# Sunfish_ECU_BulkCaps_RevA.net
KiCad netlist of a schematic drawn in Altium Designer
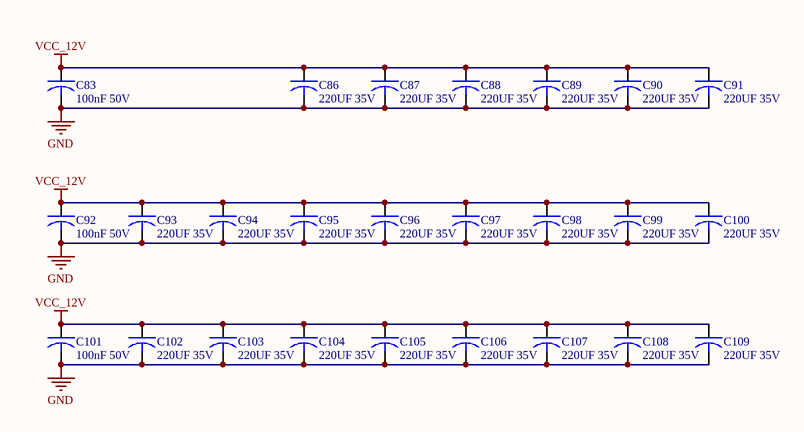
[diagram p0: Sunfish_ECU_BulkCaps_RevA.SchDoc]

(export (version "E")
  (design (tool "Eeschema 10.0.6"))
  (components
    (comp (ref "C83")
      (value "100nF 50V")
      (footprint "0603")
      (description "CAP CER 100nF 50V 10% X7R 0603")
      (fields (field (name "MANUFACTURER") "Murata"))
      (libsource (lib "Caps") (part "CAP_100NF_50V_10%_0603"))
    )
    (comp (ref "C86")
      (value "220UF 35V")
      (footprint "RB.15/.32")
      (description "CAP CER 220UF 35V 20%")
      (fields (field (name "MANUFACTURER") "Kemet"))
      (libsource (lib "Caps") (part "CAP_220UF_35V_20%"))
    )
    (comp (ref "C87")
      (value "220UF 35V")
      (footprint "RB.15/.32")
      (description "CAP CER 220UF 35V 20%")
      (fields (field (name "MANUFACTURER") "Kemet"))
      (libsource (lib "Caps") (part "CAP_220UF_35V_20%"))
    )
    (comp (ref "C88")
      (value "220UF 35V")
      (footprint "RB.15/.32")
      (description "CAP CER 220UF 35V 20%")
      (fields (field (name "MANUFACTURER") "Kemet"))
      (libsource (lib "Caps") (part "CAP_220UF_35V_20%"))
    )
    (comp (ref "C89")
      (value "220UF 35V")
      (footprint "RB.15/.32")
      (description "CAP CER 220UF 35V 20%")
      (fields (field (name "MANUFACTURER") "Kemet"))
      (libsource (lib "Caps") (part "CAP_220UF_35V_20%"))
    )
    (comp (ref "C90")
      (value "220UF 35V")
      (footprint "RB.15/.32")
      (description "CAP CER 220UF 35V 20%")
      (fields (field (name "MANUFACTURER") "Kemet"))
      (libsource (lib "Caps") (part "CAP_220UF_35V_20%"))
    )
    (comp (ref "C91")
      (value "220UF 35V")
      (footprint "RB.15/.32")
      (description "CAP CER 220UF 35V 20%")
      (fields (field (name "MANUFACTURER") "Kemet"))
      (libsource (lib "Caps") (part "CAP_220UF_35V_20%"))
    )
    (comp (ref "C92")
      (value "100nF 50V")
      (footprint "0603")
      (description "CAP CER 100nF 50V 10% X7R 0603")
      (fields (field (name "MANUFACTURER") "Murata"))
      (libsource (lib "Caps") (part "CAP_100NF_50V_10%_0603"))
    )
    (comp (ref "C93")
      (value "220UF 35V")
      (footprint "RB.15/.32")
      (description "CAP CER 220UF 35V 20%")
      (fields (field (name "MANUFACTURER") "Kemet"))
      (libsource (lib "Caps") (part "CAP_220UF_35V_20%"))
    )
    (comp (ref "C94")
      (value "220UF 35V")
      (footprint "RB.15/.32")
      (description "CAP CER 220UF 35V 20%")
      (fields (field (name "MANUFACTURER") "Kemet"))
      (libsource (lib "Caps") (part "CAP_220UF_35V_20%"))
    )
    (comp (ref "C95")
      (value "220UF 35V")
      (footprint "RB.15/.32")
      (description "CAP CER 220UF 35V 20%")
      (fields (field (name "MANUFACTURER") "Kemet"))
      (libsource (lib "Caps") (part "CAP_220UF_35V_20%"))
    )
    (comp (ref "C96")
      (value "220UF 35V")
      (footprint "RB.15/.32")
      (description "CAP CER 220UF 35V 20%")
      (fields (field (name "MANUFACTURER") "Kemet"))
      (libsource (lib "Caps") (part "CAP_220UF_35V_20%"))
    )
    (comp (ref "C97")
      (value "220UF 35V")
      (footprint "RB.15/.32")
      (description "CAP CER 220UF 35V 20%")
      (fields (field (name "MANUFACTURER") "Kemet"))
      (libsource (lib "Caps") (part "CAP_220UF_35V_20%"))
    )
    (comp (ref "C98")
      (value "220UF 35V")
      (footprint "RB.15/.32")
      (description "CAP CER 220UF 35V 20%")
      (fields (field (name "MANUFACTURER") "Kemet"))
      (libsource (lib "Caps") (part "CAP_220UF_35V_20%"))
    )
    (comp (ref "C99")
      (value "220UF 35V")
      (footprint "RB.15/.32")
      (description "CAP CER 220UF 35V 20%")
      (fields (field (name "MANUFACTURER") "Kemet"))
      (libsource (lib "Caps") (part "CAP_220UF_35V_20%"))
    )
    (comp (ref "C100")
      (value "220UF 35V")
      (footprint "RB.15/.32")
      (description "CAP CER 220UF 35V 20%")
      (fields (field (name "MANUFACTURER") "Kemet"))
      (libsource (lib "Caps") (part "CAP_220UF_35V_20%"))
    )
    (comp (ref "C101")
      (value "100nF 50V")
      (footprint "0603")
      (description "CAP CER 100nF 50V 10% X7R 0603")
      (fields (field (name "MANUFACTURER") "Murata"))
      (libsource (lib "Caps") (part "CAP_100NF_50V_10%_0603"))
    )
    (comp (ref "C102")
      (value "220UF 35V")
      (footprint "RB.15/.32")
      (description "CAP CER 220UF 35V 20%")
      (fields (field (name "MANUFACTURER") "Kemet"))
      (libsource (lib "Caps") (part "CAP_220UF_35V_20%"))
    )
    (comp (ref "C103")
      (value "220UF 35V")
      (footprint "RB.15/.32")
      (description "CAP CER 220UF 35V 20%")
      (fields (field (name "MANUFACTURER") "Kemet"))
      (libsource (lib "Caps") (part "CAP_220UF_35V_20%"))
    )
    (comp (ref "C104")
      (value "220UF 35V")
      (footprint "RB.15/.32")
      (description "CAP CER 220UF 35V 20%")
      (fields (field (name "MANUFACTURER") "Kemet"))
      (libsource (lib "Caps") (part "CAP_220UF_35V_20%"))
    )
    (comp (ref "C105")
      (value "220UF 35V")
      (footprint "RB.15/.32")
      (description "CAP CER 220UF 35V 20%")
      (fields (field (name "MANUFACTURER") "Kemet"))
      (libsource (lib "Caps") (part "CAP_220UF_35V_20%"))
    )
    (comp (ref "C106")
      (value "220UF 35V")
      (footprint "RB.15/.32")
      (description "CAP CER 220UF 35V 20%")
      (fields (field (name "MANUFACTURER") "Kemet"))
      (libsource (lib "Caps") (part "CAP_220UF_35V_20%"))
    )
    (comp (ref "C107")
      (value "220UF 35V")
      (footprint "RB.15/.32")
      (description "CAP CER 220UF 35V 20%")
      (fields (field (name "MANUFACTURER") "Kemet"))
      (libsource (lib "Caps") (part "CAP_220UF_35V_20%"))
    )
    (comp (ref "C108")
      (value "220UF 35V")
      (footprint "RB.15/.32")
      (description "CAP CER 220UF 35V 20%")
      (fields (field (name "MANUFACTURER") "Kemet"))
      (libsource (lib "Caps") (part "CAP_220UF_35V_20%"))
    )
    (comp (ref "C109")
      (value "220UF 35V")
      (footprint "RB.15/.32")
      (description "CAP CER 220UF 35V 20%")
      (fields (field (name "MANUFACTURER") "Kemet"))
      (libsource (lib "Caps") (part "CAP_220UF_35V_20%"))
    )
  )
  (nets
    (net (code "1") (name "GND") (class "Default")
      (node (ref "C100") (pin "2") (pinfunction "2_2") (pintype "passive"))
      (node (ref "C101") (pin "2") (pinfunction "2_2") (pintype "passive"))
      (node (ref "C102") (pin "2") (pinfunction "2_2") (pintype "passive"))
      (node (ref "C103") (pin "2") (pinfunction "2_2") (pintype "passive"))
      (node (ref "C104") (pin "2") (pinfunction "2_2") (pintype "passive"))
      (node (ref "C105") (pin "2") (pinfunction "2_2") (pintype "passive"))
      (node (ref "C106") (pin "2") (pinfunction "2_2") (pintype "passive"))
      (node (ref "C107") (pin "2") (pinfunction "2_2") (pintype "passive"))
      (node (ref "C108") (pin "2") (pinfunction "2_2") (pintype "passive"))
      (node (ref "C109") (pin "2") (pinfunction "2_2") (pintype "passive"))
      (node (ref "C83") (pin "2") (pinfunction "2_2") (pintype "passive"))
      (node (ref "C86") (pin "2") (pinfunction "2_2") (pintype "passive"))
      (node (ref "C87") (pin "2") (pinfunction "2_2") (pintype "passive"))
      (node (ref "C88") (pin "2") (pinfunction "2_2") (pintype "passive"))
      (node (ref "C89") (pin "2") (pinfunction "2_2") (pintype "passive"))
      (node (ref "C90") (pin "2") (pinfunction "2_2") (pintype "passive"))
      (node (ref "C91") (pin "2") (pinfunction "2_2") (pintype "passive"))
      (node (ref "C92") (pin "2") (pinfunction "2_2") (pintype "passive"))
      (node (ref "C93") (pin "2") (pinfunction "2_2") (pintype "passive"))
      (node (ref "C94") (pin "2") (pinfunction "2_2") (pintype "passive"))
      (node (ref "C95") (pin "2") (pinfunction "2_2") (pintype "passive"))
      (node (ref "C96") (pin "2") (pinfunction "2_2") (pintype "passive"))
      (node (ref "C97") (pin "2") (pinfunction "2_2") (pintype "passive"))
      (node (ref "C98") (pin "2") (pinfunction "2_2") (pintype "passive"))
      (node (ref "C99") (pin "2") (pinfunction "2_2") (pintype "passive"))
    )
    (net (code "2") (name "VCC_12V") (class "Default")
      (node (ref "C100") (pin "1") (pinfunction "1_1") (pintype "passive"))
      (node (ref "C101") (pin "1") (pinfunction "1_1") (pintype "passive"))
      (node (ref "C102") (pin "1") (pinfunction "1_1") (pintype "passive"))
      (node (ref "C103") (pin "1") (pinfunction "1_1") (pintype "passive"))
      (node (ref "C104") (pin "1") (pinfunction "1_1") (pintype "passive"))
      (node (ref "C105") (pin "1") (pinfunction "1_1") (pintype "passive"))
      (node (ref "C106") (pin "1") (pinfunction "1_1") (pintype "passive"))
      (node (ref "C107") (pin "1") (pinfunction "1_1") (pintype "passive"))
      (node (ref "C108") (pin "1") (pinfunction "1_1") (pintype "passive"))
      (node (ref "C109") (pin "1") (pinfunction "1_1") (pintype "passive"))
      (node (ref "C83") (pin "1") (pinfunction "1_1") (pintype "passive"))
      (node (ref "C86") (pin "1") (pinfunction "1_1") (pintype "passive"))
      (node (ref "C87") (pin "1") (pinfunction "1_1") (pintype "passive"))
      (node (ref "C88") (pin "1") (pinfunction "1_1") (pintype "passive"))
      (node (ref "C89") (pin "1") (pinfunction "1_1") (pintype "passive"))
      (node (ref "C90") (pin "1") (pinfunction "1_1") (pintype "passive"))
      (node (ref "C91") (pin "1") (pinfunction "1_1") (pintype "passive"))
      (node (ref "C92") (pin "1") (pinfunction "1_1") (pintype "passive"))
      (node (ref "C93") (pin "1") (pinfunction "1_1") (pintype "passive"))
      (node (ref "C94") (pin "1") (pinfunction "1_1") (pintype "passive"))
      (node (ref "C95") (pin "1") (pinfunction "1_1") (pintype "passive"))
      (node (ref "C96") (pin "1") (pinfunction "1_1") (pintype "passive"))
      (node (ref "C97") (pin "1") (pinfunction "1_1") (pintype "passive"))
      (node (ref "C98") (pin "1") (pinfunction "1_1") (pintype "passive"))
      (node (ref "C99") (pin "1") (pinfunction "1_1") (pintype "passive"))
    )
  )
)
